# CM4_IO_Conn.net
KiCad netlist of a schematic drawn in Altium Designer
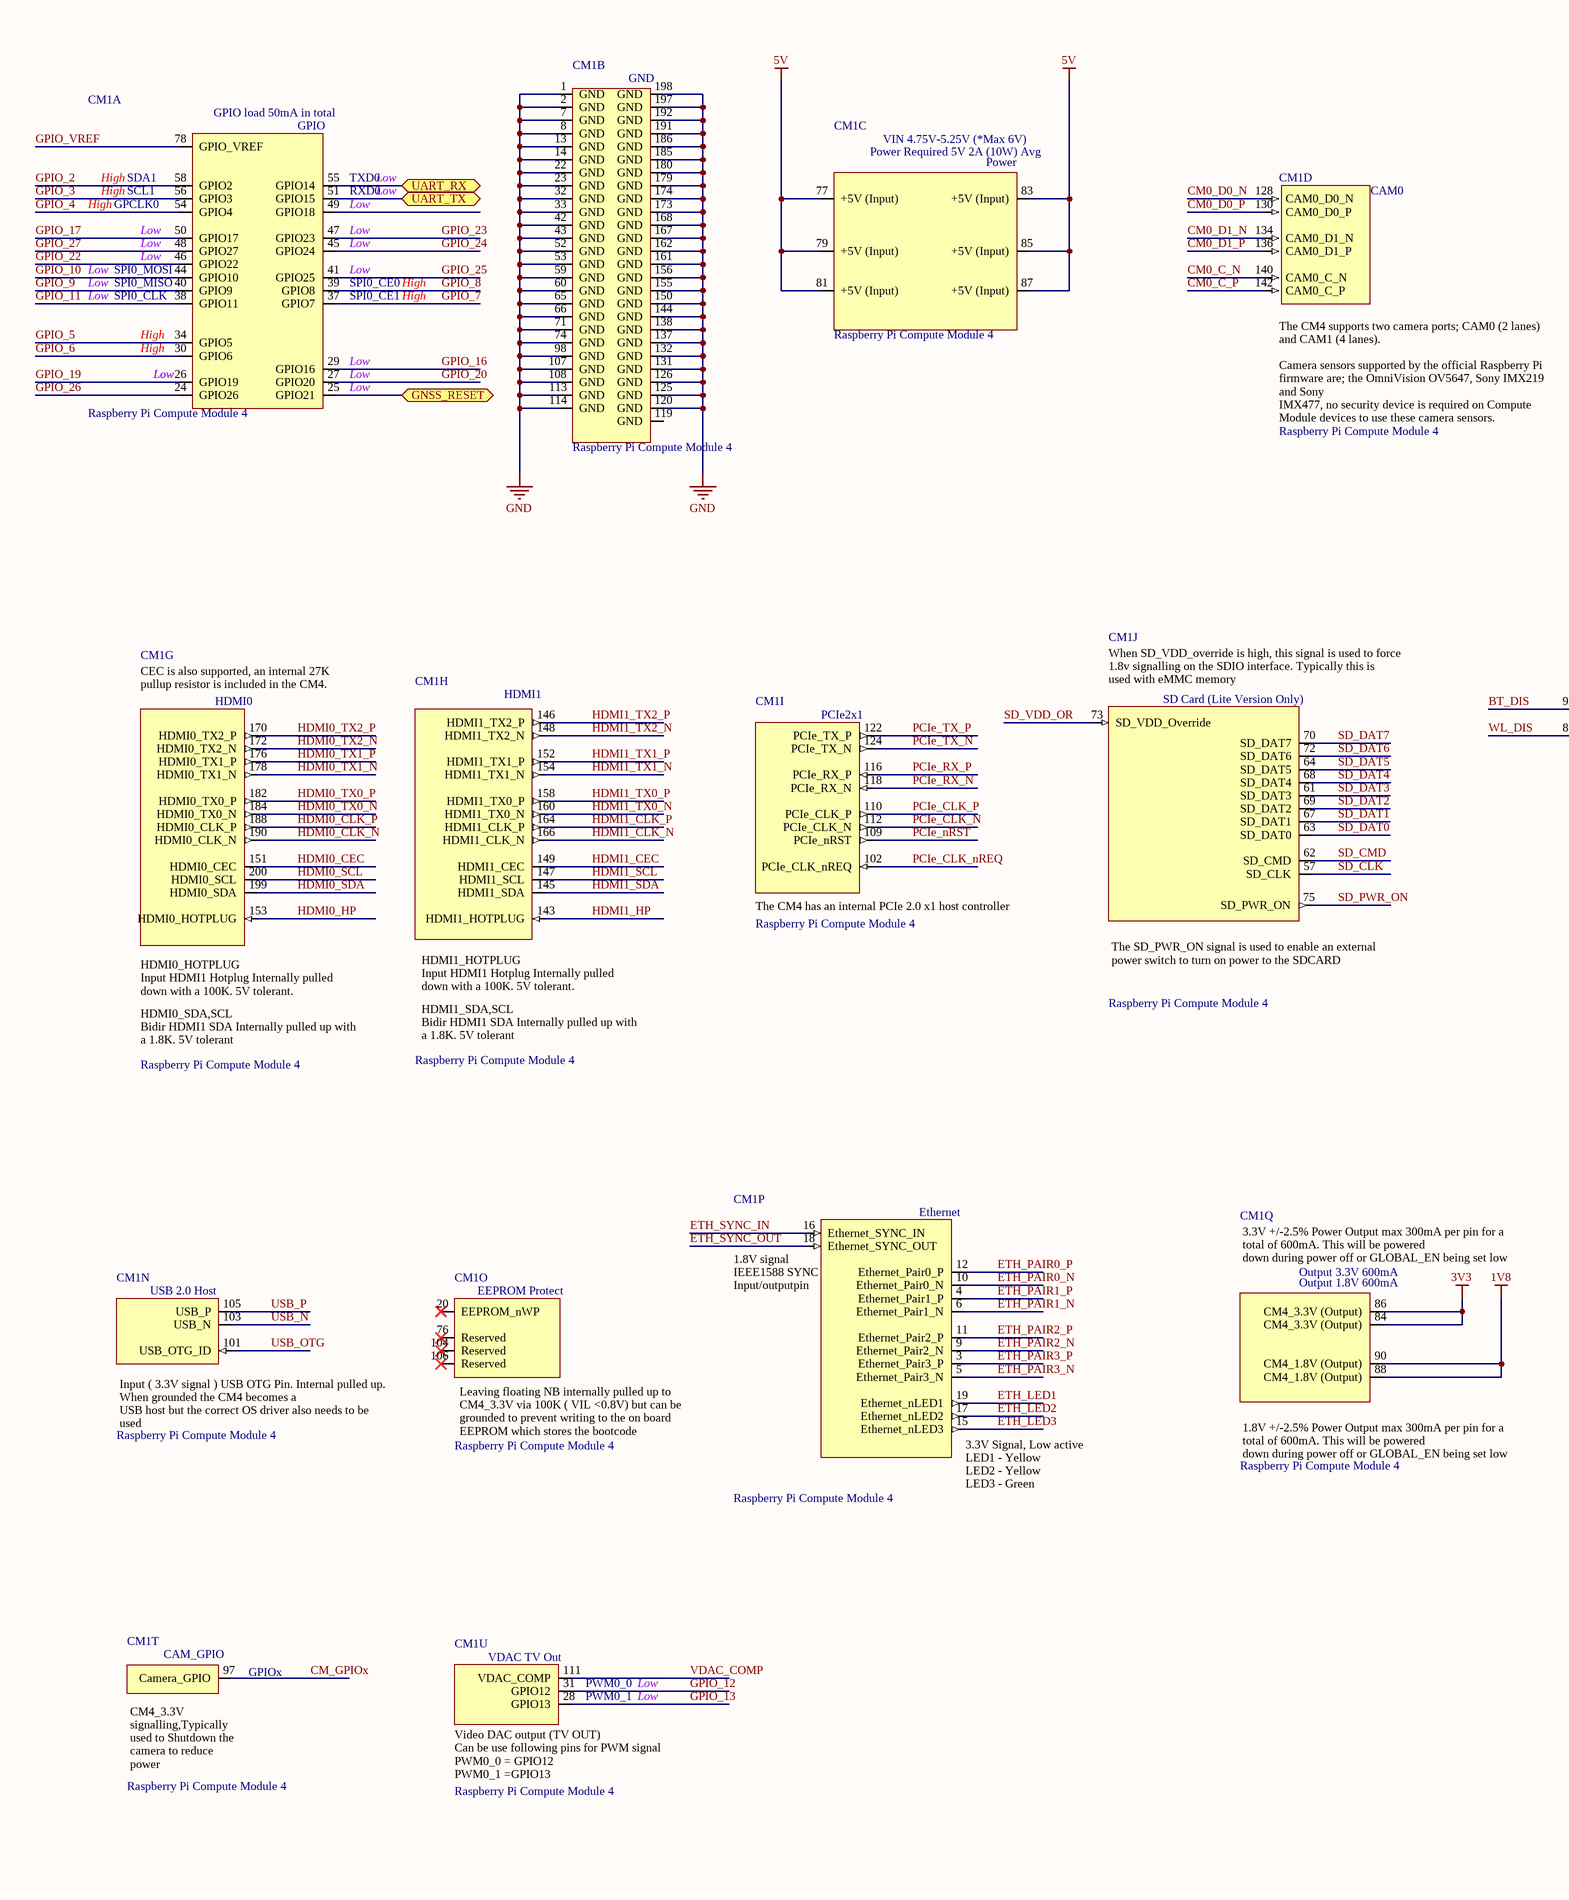
[diagram p0: CM4_IO_Conn.SchDoc, left]
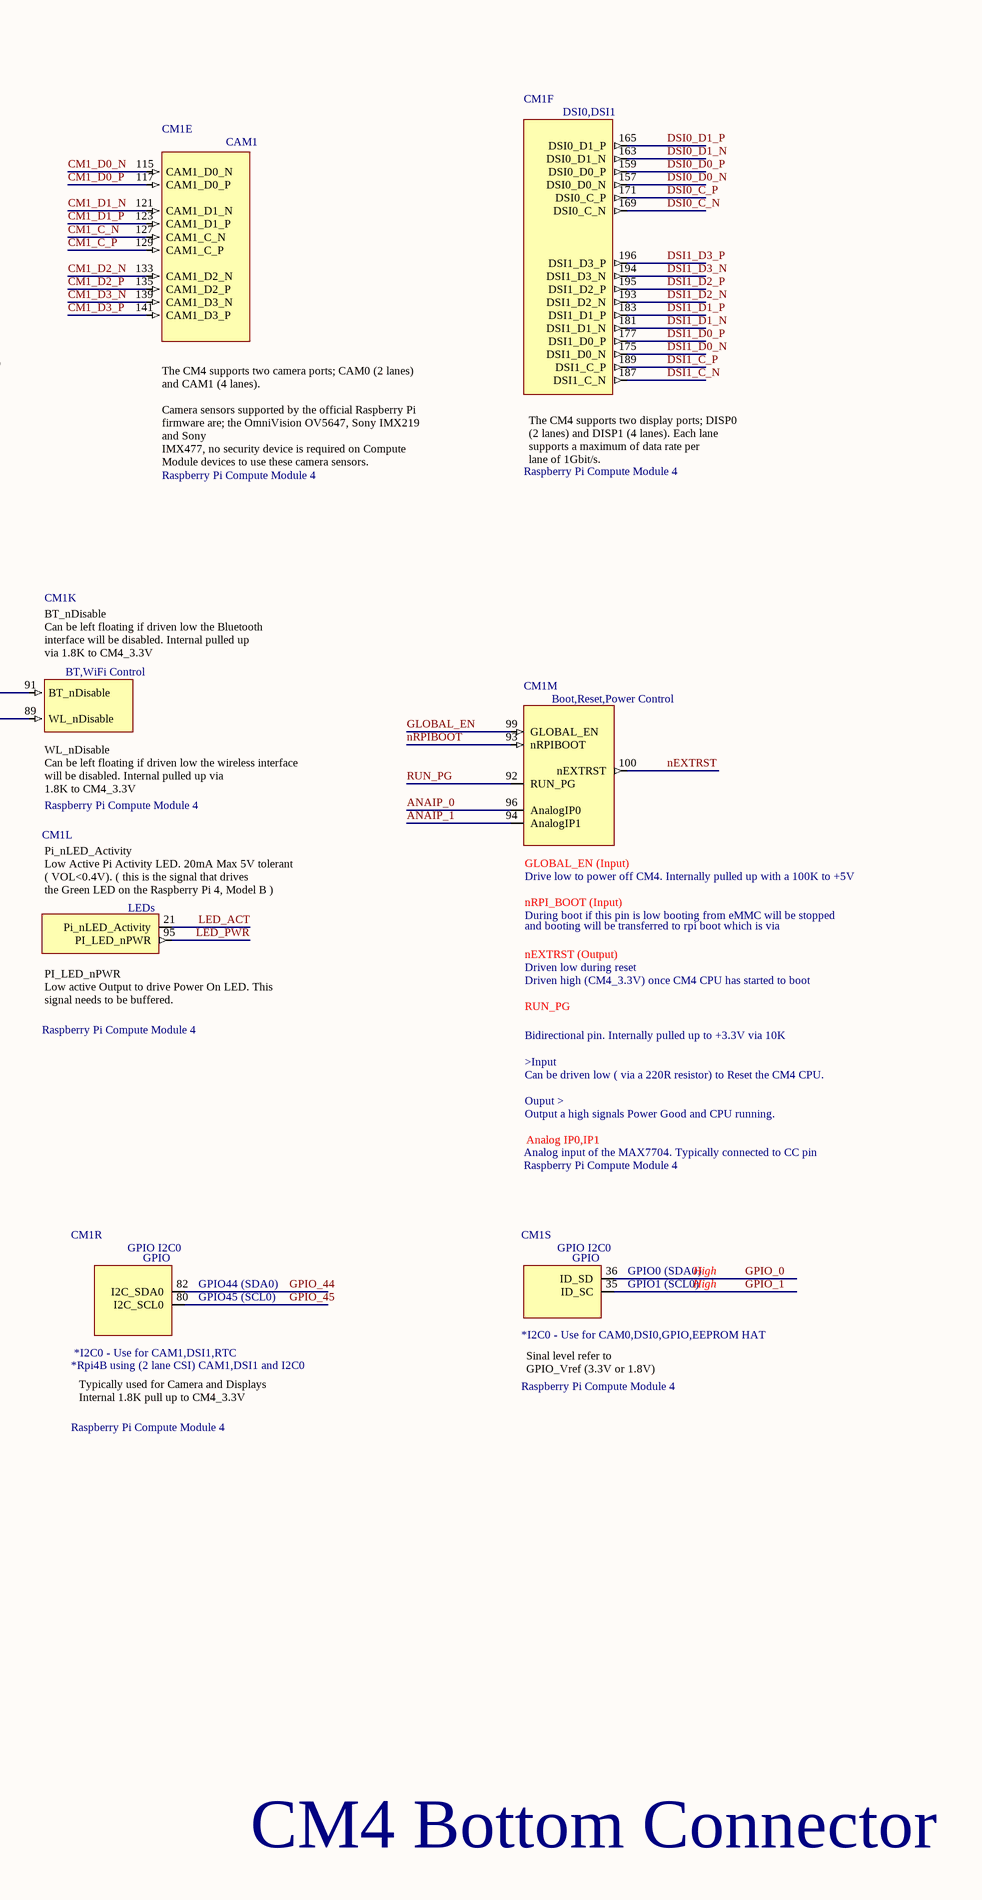
[diagram p1: CM4_IO_Conn.SchDoc, right]

(export (version "E")
  (design (tool "Eeschema 10.0.6"))
  (components
    (comp (ref "CM1")
      (value "Raspberry Pi Compute Module 4")
      (footprint "CM4-F40C-100DS-0.4v_1.5mm_0mm")
      (description "Raspberry Pi Compute Module 4 by Amornthep Phunsin")
      (libsource (lib "CM4") (part "CM4"))
    )
  )
  (nets
    (net (code "1") (name "/ANAIP_0") (class "Default")
      (node (ref "CM1") (pin "96") (pinfunction "AnalogIP0_96") (pintype "passive"))
    )
    (net (code "2") (name "/ANAIP_1") (class "Default")
      (node (ref "CM1") (pin "94") (pinfunction "AnalogIP1_94") (pintype "passive"))
    )
    (net (code "3") (name "/BT_DIS") (class "Default")
      (node (ref "CM1") (pin "91") (pinfunction "BT_nDisable_91") (pintype "input"))
    )
    (net (code "4") (name "/CM0_C_N") (class "Default")
      (node (ref "CM1") (pin "140") (pinfunction "CAM0_C_N_140") (pintype "input"))
    )
    (net (code "5") (name "/CM0_C_P") (class "Default")
      (node (ref "CM1") (pin "142") (pinfunction "CAM0_C_P_142") (pintype "input"))
    )
    (net (code "6") (name "/CM0_D0_N") (class "Default")
      (node (ref "CM1") (pin "128") (pinfunction "CAM0_D0_N_128") (pintype "input"))
    )
    (net (code "7") (name "/CM0_D0_P") (class "Default")
      (node (ref "CM1") (pin "130") (pinfunction "CAM0_D0_P_130") (pintype "input"))
    )
    (net (code "8") (name "/CM0_D1_N") (class "Default")
      (node (ref "CM1") (pin "134") (pinfunction "CAM0_D1_N_134") (pintype "input"))
    )
    (net (code "9") (name "/CM0_D1_P") (class "Default")
      (node (ref "CM1") (pin "136") (pinfunction "CAM0_D1_P_136") (pintype "input"))
    )
    (net (code "10") (name "/CM1_C_N") (class "Default")
      (node (ref "CM1") (pin "127") (pinfunction "CAM1_C_N_127") (pintype "input"))
    )
    (net (code "11") (name "/CM1_C_P") (class "Default")
      (node (ref "CM1") (pin "129") (pinfunction "CAM1_C_P_129") (pintype "input"))
    )
    (net (code "12") (name "/CM1_D0_N") (class "Default")
      (node (ref "CM1") (pin "115") (pinfunction "CAM1_D0_N_115") (pintype "input"))
    )
    (net (code "13") (name "/CM1_D0_P") (class "Default")
      (node (ref "CM1") (pin "117") (pinfunction "CAM1_D0_P_117") (pintype "input"))
    )
    (net (code "14") (name "/CM1_D1_N") (class "Default")
      (node (ref "CM1") (pin "121") (pinfunction "CAM1_D1_N_121") (pintype "input"))
    )
    (net (code "15") (name "/CM1_D1_P") (class "Default")
      (node (ref "CM1") (pin "123") (pinfunction "CAM1_D1_P_123") (pintype "input"))
    )
    (net (code "16") (name "/CM1_D2_N") (class "Default")
      (node (ref "CM1") (pin "133") (pinfunction "CAM1_D2_N_133") (pintype "input"))
    )
    (net (code "17") (name "/CM1_D2_P") (class "Default")
      (node (ref "CM1") (pin "135") (pinfunction "CAM1_D2_P_135") (pintype "input"))
    )
    (net (code "18") (name "/CM1_D3_N") (class "Default")
      (node (ref "CM1") (pin "139") (pinfunction "CAM1_D3_N_139") (pintype "input"))
    )
    (net (code "19") (name "/CM1_D3_P") (class "Default")
      (node (ref "CM1") (pin "141") (pinfunction "CAM1_D3_P_141") (pintype "input"))
    )
    (net (code "20") (name "/CM_GPIOx") (class "Default")
      (node (ref "CM1") (pin "97") (pinfunction "Camera_GPIO_97") (pintype "passive"))
    )
    (net (code "21") (name "/DSI0_C_N") (class "Default")
      (node (ref "CM1") (pin "169") (pinfunction "DSI0_C_N_169") (pintype "output"))
    )
    (net (code "22") (name "/DSI0_C_P") (class "Default")
      (node (ref "CM1") (pin "171") (pinfunction "DSI0_C_P_171") (pintype "output"))
    )
    (net (code "23") (name "/DSI0_D0_N") (class "Default")
      (node (ref "CM1") (pin "157") (pinfunction "DSI0_D0_N_157") (pintype "output"))
    )
    (net (code "24") (name "/DSI0_D0_P") (class "Default")
      (node (ref "CM1") (pin "159") (pinfunction "DSI0_D0_P_159") (pintype "output"))
    )
    (net (code "25") (name "/DSI0_D1_N") (class "Default")
      (node (ref "CM1") (pin "163") (pinfunction "DSI0_D1_N_163") (pintype "output"))
    )
    (net (code "26") (name "/DSI0_D1_P") (class "Default")
      (node (ref "CM1") (pin "165") (pinfunction "DSI0_D1_P_165") (pintype "output"))
    )
    (net (code "27") (name "/DSI1_C_N") (class "Default")
      (node (ref "CM1") (pin "187") (pinfunction "DSI1_C_N_187") (pintype "output"))
    )
    (net (code "28") (name "/DSI1_C_P") (class "Default")
      (node (ref "CM1") (pin "189") (pinfunction "DSI1_C_P_189") (pintype "output"))
    )
    (net (code "29") (name "/DSI1_D0_N") (class "Default")
      (node (ref "CM1") (pin "175") (pinfunction "DSI1_D0_N_175") (pintype "output"))
    )
    (net (code "30") (name "/DSI1_D0_P") (class "Default")
      (node (ref "CM1") (pin "177") (pinfunction "DSI1_D0_P_177") (pintype "output"))
    )
    (net (code "31") (name "/DSI1_D1_N") (class "Default")
      (node (ref "CM1") (pin "181") (pinfunction "DSI1_D1_N_181") (pintype "output"))
    )
    (net (code "32") (name "/DSI1_D1_P") (class "Default")
      (node (ref "CM1") (pin "183") (pinfunction "DSI1_D1_P_183") (pintype "output"))
    )
    (net (code "33") (name "/DSI1_D2_N") (class "Default")
      (node (ref "CM1") (pin "193") (pinfunction "DSI1_D2_N_193") (pintype "output"))
    )
    (net (code "34") (name "/DSI1_D2_P") (class "Default")
      (node (ref "CM1") (pin "195") (pinfunction "DSI1_D2_P_195") (pintype "output"))
    )
    (net (code "35") (name "/DSI1_D3_N") (class "Default")
      (node (ref "CM1") (pin "194") (pinfunction "DSI1_D3_N_194") (pintype "output"))
    )
    (net (code "36") (name "/DSI1_D3_P") (class "Default")
      (node (ref "CM1") (pin "196") (pinfunction "DSI1_D3_P_196") (pintype "output"))
    )
    (net (code "37") (name "/ETH_LED1") (class "Default")
      (node (ref "CM1") (pin "19") (pinfunction "Ethernet_nLED1_19") (pintype "output"))
    )
    (net (code "38") (name "/ETH_LED2") (class "Default")
      (node (ref "CM1") (pin "17") (pinfunction "Ethernet_nLED2_17") (pintype "output"))
    )
    (net (code "39") (name "/ETH_LED3") (class "Default")
      (node (ref "CM1") (pin "15") (pinfunction "Ethernet_nLED3_15") (pintype "output"))
    )
    (net (code "40") (name "/ETH_PAIR0_N") (class "Default")
      (node (ref "CM1") (pin "10") (pinfunction "Ethernet_Pair0_N_10") (pintype "passive"))
    )
    (net (code "41") (name "/ETH_PAIR0_P") (class "Default")
      (node (ref "CM1") (pin "12") (pinfunction "Ethernet_Pair0_P_12") (pintype "passive"))
    )
    (net (code "42") (name "/ETH_PAIR1_N") (class "Default")
      (node (ref "CM1") (pin "6") (pinfunction "Ethernet_Pair1_N_6") (pintype "passive"))
    )
    (net (code "43") (name "/ETH_PAIR1_P") (class "Default")
      (node (ref "CM1") (pin "4") (pinfunction "Ethernet_Pair1_P_4") (pintype "passive"))
    )
    (net (code "44") (name "/ETH_PAIR2_N") (class "Default")
      (node (ref "CM1") (pin "9") (pinfunction "Ethernet_Pair2_N_9") (pintype "passive"))
    )
    (net (code "45") (name "/ETH_PAIR2_P") (class "Default")
      (node (ref "CM1") (pin "11") (pinfunction "Ethernet_Pair2_P_11") (pintype "passive"))
    )
    (net (code "46") (name "/ETH_PAIR3_N") (class "Default")
      (node (ref "CM1") (pin "5") (pinfunction "Ethernet_Pair3_N_5") (pintype "passive"))
    )
    (net (code "47") (name "/ETH_PAIR3_P") (class "Default")
      (node (ref "CM1") (pin "3") (pinfunction "Ethernet_Pair3_P_3") (pintype "passive"))
    )
    (net (code "48") (name "/ETH_SYNC_IN") (class "Default")
      (node (ref "CM1") (pin "16") (pinfunction "Ethernet_SYNC_IN_16") (pintype "input"))
    )
    (net (code "49") (name "/ETH_SYNC_OUT") (class "Default")
      (node (ref "CM1") (pin "18") (pinfunction "Ethernet_SYNC_OUT_18") (pintype "input"))
    )
    (net (code "50") (name "/GLOBAL_EN") (class "Default")
      (node (ref "CM1") (pin "99") (pinfunction "GLOBAL_EN_99") (pintype "input"))
    )
    (net (code "51") (name "/GNSS_RESET") (class "Default")
      (node (ref "CM1") (pin "25") (pinfunction "GPIO21_25") (pintype "passive"))
    )
    (net (code "52") (name "/GPIO_0") (class "Default")
      (node (ref "CM1") (pin "36") (pinfunction "ID_SD_36") (pintype "passive"))
    )
    (net (code "53") (name "/GPIO_1") (class "Default")
      (node (ref "CM1") (pin "35") (pinfunction "ID_SC_35") (pintype "passive"))
    )
    (net (code "54") (name "/GPIO_2") (class "Default")
      (node (ref "CM1") (pin "58") (pinfunction "GPIO2_58") (pintype "passive"))
    )
    (net (code "55") (name "/GPIO_3") (class "Default")
      (node (ref "CM1") (pin "56") (pinfunction "GPIO3_56") (pintype "passive"))
    )
    (net (code "56") (name "/GPIO_4") (class "Default")
      (node (ref "CM1") (pin "54") (pinfunction "GPIO4_54") (pintype "passive"))
    )
    (net (code "57") (name "/GPIO_5") (class "Default")
      (node (ref "CM1") (pin "34") (pinfunction "GPIO5_34") (pintype "passive"))
    )
    (net (code "58") (name "/GPIO_6") (class "Default")
      (node (ref "CM1") (pin "30") (pinfunction "GPIO6_30") (pintype "passive"))
    )
    (net (code "59") (name "/GPIO_7") (class "Default")
      (node (ref "CM1") (pin "37") (pinfunction "GPIO7_37") (pintype "passive"))
    )
    (net (code "60") (name "/GPIO_8") (class "Default")
      (node (ref "CM1") (pin "39") (pinfunction "GPIO8_39") (pintype "passive"))
    )
    (net (code "61") (name "/GPIO_9") (class "Default")
      (node (ref "CM1") (pin "40") (pinfunction "GPIO9_40") (pintype "passive"))
    )
    (net (code "62") (name "/GPIO_10") (class "Default")
      (node (ref "CM1") (pin "44") (pinfunction "GPIO10_44") (pintype "passive"))
    )
    (net (code "63") (name "/GPIO_11") (class "Default")
      (node (ref "CM1") (pin "38") (pinfunction "GPIO11_38") (pintype "passive"))
    )
    (net (code "64") (name "/GPIO_12") (class "Default")
      (node (ref "CM1") (pin "31") (pinfunction "GPIO12_31") (pintype "passive"))
    )
    (net (code "65") (name "/GPIO_13") (class "Default")
      (node (ref "CM1") (pin "28") (pinfunction "GPIO13_28") (pintype "passive"))
    )
    (net (code "66") (name "/GPIO_16") (class "Default")
      (node (ref "CM1") (pin "29") (pinfunction "GPIO16_29") (pintype "passive"))
    )
    (net (code "67") (name "/GPIO_17") (class "Default")
      (node (ref "CM1") (pin "50") (pinfunction "GPIO17_50") (pintype "passive"))
    )
    (net (code "68") (name "/GPIO_19") (class "Default")
      (node (ref "CM1") (pin "26") (pinfunction "GPIO19_26") (pintype "passive"))
    )
    (net (code "69") (name "/GPIO_20") (class "Default")
      (node (ref "CM1") (pin "27") (pinfunction "GPIO20_27") (pintype "passive"))
    )
    (net (code "70") (name "/GPIO_22") (class "Default")
      (node (ref "CM1") (pin "46") (pinfunction "GPIO22_46") (pintype "passive"))
    )
    (net (code "71") (name "/GPIO_23") (class "Default")
      (node (ref "CM1") (pin "47") (pinfunction "GPIO23_47") (pintype "passive"))
    )
    (net (code "72") (name "/GPIO_24") (class "Default")
      (node (ref "CM1") (pin "45") (pinfunction "GPIO24_45") (pintype "passive"))
    )
    (net (code "73") (name "/GPIO_25") (class "Default")
      (node (ref "CM1") (pin "41") (pinfunction "GPIO25_41") (pintype "passive"))
    )
    (net (code "74") (name "/GPIO_26") (class "Default")
      (node (ref "CM1") (pin "24") (pinfunction "GPIO26_24") (pintype "passive"))
    )
    (net (code "75") (name "/GPIO_27") (class "Default")
      (node (ref "CM1") (pin "48") (pinfunction "GPIO27_48") (pintype "passive"))
    )
    (net (code "76") (name "/GPIO_44") (class "Default")
      (node (ref "CM1") (pin "82") (pinfunction "I2C_SDA0_82") (pintype "passive"))
    )
    (net (code "77") (name "/GPIO_45") (class "Default")
      (node (ref "CM1") (pin "80") (pinfunction "I2C_SCL0_80") (pintype "passive"))
    )
    (net (code "78") (name "/GPIO_VREF") (class "Default")
      (node (ref "CM1") (pin "78") (pinfunction "GPIO_VREF_78") (pintype "power_in"))
    )
    (net (code "79") (name "/HDMI0_CEC") (class "Default")
      (node (ref "CM1") (pin "151") (pinfunction "HDMI0_CEC_151") (pintype "open_collector"))
    )
    (net (code "80") (name "/HDMI0_CLK_N") (class "Default")
      (node (ref "CM1") (pin "190") (pinfunction "HDMI0_CLK_N_190") (pintype "output"))
    )
    (net (code "81") (name "/HDMI0_CLK_P") (class "Default")
      (node (ref "CM1") (pin "188") (pinfunction "HDMI0_CLK_P_188") (pintype "output"))
    )
    (net (code "82") (name "/HDMI0_HP") (class "Default")
      (node (ref "CM1") (pin "153") (pinfunction "HDMI0_HOTPLUG_153") (pintype "input"))
    )
    (net (code "83") (name "/HDMI0_SCL") (class "Default")
      (node (ref "CM1") (pin "200") (pinfunction "HDMI0_SCL_200") (pintype "open_collector"))
    )
    (net (code "84") (name "/HDMI0_SDA") (class "Default")
      (node (ref "CM1") (pin "199") (pinfunction "HDMI0_SDA_199") (pintype "bidirectional"))
    )
    (net (code "85") (name "/HDMI0_TX0_N") (class "Default")
      (node (ref "CM1") (pin "184") (pinfunction "HDMI0_TX0_N_184") (pintype "output"))
    )
    (net (code "86") (name "/HDMI0_TX0_P") (class "Default")
      (node (ref "CM1") (pin "182") (pinfunction "HDMI0_TX0_P_182") (pintype "output"))
    )
    (net (code "87") (name "/HDMI0_TX1_N") (class "Default")
      (node (ref "CM1") (pin "178") (pinfunction "HDMI0_TX1_N_178") (pintype "output"))
    )
    (net (code "88") (name "/HDMI0_TX1_P") (class "Default")
      (node (ref "CM1") (pin "176") (pinfunction "HDMI0_TX1_P_176") (pintype "output"))
    )
    (net (code "89") (name "/HDMI0_TX2_N") (class "Default")
      (node (ref "CM1") (pin "172") (pinfunction "HDMI0_TX2_N_172") (pintype "output"))
    )
    (net (code "90") (name "/HDMI0_TX2_P") (class "Default")
      (node (ref "CM1") (pin "170") (pinfunction "HDMI0_TX2_P_170") (pintype "output"))
    )
    (net (code "91") (name "/HDMI1_CEC") (class "Default")
      (node (ref "CM1") (pin "149") (pinfunction "HDMI1_CEC_149") (pintype "open_collector"))
    )
    (net (code "92") (name "/HDMI1_CLK_N") (class "Default")
      (node (ref "CM1") (pin "166") (pinfunction "HDMI1_CLK_N_166") (pintype "output"))
    )
    (net (code "93") (name "/HDMI1_CLK_P") (class "Default")
      (node (ref "CM1") (pin "164") (pinfunction "HDMI1_CLK_P_164") (pintype "output"))
    )
    (net (code "94") (name "/HDMI1_HP") (class "Default")
      (node (ref "CM1") (pin "143") (pinfunction "HDMI1_HOTPLUG_143") (pintype "input"))
    )
    (net (code "95") (name "/HDMI1_SCL") (class "Default")
      (node (ref "CM1") (pin "147") (pinfunction "HDMI1_SCL_147") (pintype "open_collector"))
    )
    (net (code "96") (name "/HDMI1_SDA") (class "Default")
      (node (ref "CM1") (pin "145") (pinfunction "HDMI1_SDA_145") (pintype "bidirectional"))
    )
    (net (code "97") (name "/HDMI1_TX0_N") (class "Default")
      (node (ref "CM1") (pin "160") (pinfunction "HDMI1_TX0_N_160") (pintype "output"))
    )
    (net (code "98") (name "/HDMI1_TX0_P") (class "Default")
      (node (ref "CM1") (pin "158") (pinfunction "HDMI1_TX0_P_158") (pintype "output"))
    )
    (net (code "99") (name "/HDMI1_TX1_N") (class "Default")
      (node (ref "CM1") (pin "154") (pinfunction "HDMI1_TX1_N_154") (pintype "output"))
    )
    (net (code "100") (name "/HDMI1_TX1_P") (class "Default")
      (node (ref "CM1") (pin "152") (pinfunction "HDMI1_TX1_P_152") (pintype "output"))
    )
    (net (code "101") (name "/HDMI1_TX2_N") (class "Default")
      (node (ref "CM1") (pin "148") (pinfunction "HDMI1_TX2_N_148") (pintype "output"))
    )
    (net (code "102") (name "/HDMI1_TX2_P") (class "Default")
      (node (ref "CM1") (pin "146") (pinfunction "HDMI1_TX2_P_146") (pintype "output"))
    )
    (net (code "103") (name "/LED_ACT") (class "Default")
      (node (ref "CM1") (pin "21") (pinfunction "Pi_nLED_Activity_21") (pintype "open_collector"))
    )
    (net (code "104") (name "/LED_PWR") (class "Default")
      (node (ref "CM1") (pin "95") (pinfunction "PI_LED_nPWR_95") (pintype "output"))
    )
    (net (code "105") (name "/PCIe_CLK_N") (class "Default")
      (node (ref "CM1") (pin "112") (pinfunction "PCIe_CLK_N_112") (pintype "output"))
    )
    (net (code "106") (name "/PCIe_CLK_P") (class "Default")
      (node (ref "CM1") (pin "110") (pinfunction "PCIe_CLK_P_110") (pintype "output"))
    )
    (net (code "107") (name "/PCIe_CLK_nREQ") (class "Default")
      (node (ref "CM1") (pin "102") (pinfunction "PCIe_CLK_nREQ_102") (pintype "input"))
    )
    (net (code "108") (name "/PCIe_RX_N") (class "Default")
      (node (ref "CM1") (pin "118") (pinfunction "PCIe_RX_N_118") (pintype "input"))
    )
    (net (code "109") (name "/PCIe_RX_P") (class "Default")
      (node (ref "CM1") (pin "116") (pinfunction "PCIe_RX_P_116") (pintype "input"))
    )
    (net (code "110") (name "/PCIe_TX_N") (class "Default")
      (node (ref "CM1") (pin "124") (pinfunction "PCIe_TX_N_124") (pintype "output"))
    )
    (net (code "111") (name "/PCIe_TX_P") (class "Default")
      (node (ref "CM1") (pin "122") (pinfunction "PCIe_TX_P_122") (pintype "output"))
    )
    (net (code "112") (name "/PCIe_nRST") (class "Default")
      (node (ref "CM1") (pin "109") (pinfunction "PCIe_nRST_109") (pintype "output"))
    )
    (net (code "113") (name "/RUN_PG") (class "Default")
      (node (ref "CM1") (pin "92") (pinfunction "RUN_PG_92") (pintype "passive"))
    )
    (net (code "114") (name "/SD_CLK") (class "Default")
      (node (ref "CM1") (pin "57") (pinfunction "SD_CLK_57") (pintype "passive"))
    )
    (net (code "115") (name "/SD_CMD") (class "Default")
      (node (ref "CM1") (pin "62") (pinfunction "SD_CMD_62") (pintype "passive"))
    )
    (net (code "116") (name "/SD_DAT0") (class "Default")
      (node (ref "CM1") (pin "63") (pinfunction "SD_DAT0_63") (pintype "passive"))
    )
    (net (code "117") (name "/SD_DAT1") (class "Default")
      (node (ref "CM1") (pin "67") (pinfunction "SD_DAT1_67") (pintype "passive"))
    )
    (net (code "118") (name "/SD_DAT2") (class "Default")
      (node (ref "CM1") (pin "69") (pinfunction "SD_DAT2_69") (pintype "passive"))
    )
    (net (code "119") (name "/SD_DAT3") (class "Default")
      (node (ref "CM1") (pin "61") (pinfunction "SD_DAT3_61") (pintype "passive"))
    )
    (net (code "120") (name "/SD_DAT4") (class "Default")
      (node (ref "CM1") (pin "68") (pinfunction "SD_DAT4_68") (pintype "passive"))
    )
    (net (code "121") (name "/SD_DAT5") (class "Default")
      (node (ref "CM1") (pin "64") (pinfunction "SD_DAT5_64") (pintype "passive"))
    )
    (net (code "122") (name "/SD_DAT6") (class "Default")
      (node (ref "CM1") (pin "72") (pinfunction "SD_DAT6_72") (pintype "passive"))
    )
    (net (code "123") (name "/SD_DAT7") (class "Default")
      (node (ref "CM1") (pin "70") (pinfunction "SD_DAT7_70") (pintype "passive"))
    )
    (net (code "124") (name "/SD_PWR_ON") (class "Default")
      (node (ref "CM1") (pin "75") (pinfunction "SD_PWR_ON_75") (pintype "output"))
    )
    (net (code "125") (name "/SD_VDD_OR") (class "Default")
      (node (ref "CM1") (pin "73") (pinfunction "SD_VDD_Override_73") (pintype "input"))
    )
    (net (code "126") (name "/UART_RX") (class "Default")
      (node (ref "CM1") (pin "55") (pinfunction "GPIO14_55") (pintype "passive"))
    )
    (net (code "127") (name "/UART_TX") (class "Default")
      (node (ref "CM1") (pin "51") (pinfunction "GPIO15_51") (pintype "passive"))
    )
    (net (code "128") (name "/USB_N") (class "Default")
      (node (ref "CM1") (pin "103") (pinfunction "USB_N_103") (pintype "passive"))
    )
    (net (code "129") (name "/USB_OTG") (class "Default")
      (node (ref "CM1") (pin "101") (pinfunction "USB_OTG_ID_101") (pintype "input"))
    )
    (net (code "130") (name "/USB_P") (class "Default")
      (node (ref "CM1") (pin "105") (pinfunction "USB_P_105") (pintype "passive"))
    )
    (net (code "131") (name "/VDAC_COMP") (class "Default")
      (node (ref "CM1") (pin "111") (pinfunction "VDAC_COMP_111") (pintype "passive"))
    )
    (net (code "132") (name "/WL_DIS") (class "Default")
      (node (ref "CM1") (pin "89") (pinfunction "WL_nDisable_89") (pintype "input"))
    )
    (net (code "133") (name "/nEXTRST") (class "Default")
      (node (ref "CM1") (pin "100") (pinfunction "nEXTRST_100") (pintype "output"))
    )
    (net (code "134") (name "/nRPIBOOT") (class "Default")
      (node (ref "CM1") (pin "93") (pinfunction "nRPIBOOT_93") (pintype "input"))
    )
    (net (code "135") (name "1V8") (class "Default")
      (node (ref "CM1") (pin "88") (pinfunction "CM4_1.8V_(Output)_88") (pintype "power_in"))
      (node (ref "CM1") (pin "90") (pinfunction "CM4_1.8V_(Output)_90") (pintype "power_in"))
    )
    (net (code "136") (name "3V3") (class "Default")
      (node (ref "CM1") (pin "84") (pinfunction "CM4_3.3V_(Output)_84") (pintype "power_in"))
      (node (ref "CM1") (pin "86") (pinfunction "CM4_3.3V_(Output)_86") (pintype "power_in"))
    )
    (net (code "137") (name "5V") (class "Default")
      (node (ref "CM1") (pin "77") (pinfunction "+5V_(Input)_77") (pintype "power_in"))
      (node (ref "CM1") (pin "79") (pinfunction "+5V_(Input)_79") (pintype "power_in"))
      (node (ref "CM1") (pin "81") (pinfunction "+5V_(Input)_81") (pintype "power_in"))
      (node (ref "CM1") (pin "83") (pinfunction "+5V_(Input)_83") (pintype "power_in"))
      (node (ref "CM1") (pin "85") (pinfunction "+5V_(Input)_85") (pintype "power_in"))
      (node (ref "CM1") (pin "87") (pinfunction "+5V_(Input)_87") (pintype "power_in"))
    )
    (net (code "138") (name "GND") (class "Default")
      (node (ref "CM1") (pin "1") (pinfunction "GND_1") (pintype "power_in"))
      (node (ref "CM1") (pin "107") (pinfunction "GND_107") (pintype "power_in"))
      (node (ref "CM1") (pin "108") (pinfunction "GND_108") (pintype "power_in"))
      (node (ref "CM1") (pin "113") (pinfunction "GND_113") (pintype "power_in"))
      (node (ref "CM1") (pin "114") (pinfunction "GND_114") (pintype "power_in"))
      (node (ref "CM1") (pin "120") (pinfunction "GND_120") (pintype "power_in"))
      (node (ref "CM1") (pin "125") (pinfunction "GND_125") (pintype "power_in"))
      (node (ref "CM1") (pin "126") (pinfunction "GND_126") (pintype "power_in"))
      (node (ref "CM1") (pin "13") (pinfunction "GND_13") (pintype "power_in"))
      (node (ref "CM1") (pin "131") (pinfunction "GND_131") (pintype "power_in"))
      (node (ref "CM1") (pin "132") (pinfunction "GND_132") (pintype "power_in"))
      (node (ref "CM1") (pin "137") (pinfunction "GND_137") (pintype "power_in"))
      (node (ref "CM1") (pin "138") (pinfunction "GND_138") (pintype "power_in"))
      (node (ref "CM1") (pin "14") (pinfunction "GND_14") (pintype "power_in"))
      (node (ref "CM1") (pin "144") (pinfunction "GND_144") (pintype "power_in"))
      (node (ref "CM1") (pin "150") (pinfunction "GND_150") (pintype "power_in"))
      (node (ref "CM1") (pin "155") (pinfunction "GND_155") (pintype "power_in"))
      (node (ref "CM1") (pin "156") (pinfunction "GND_156") (pintype "power_in"))
      (node (ref "CM1") (pin "161") (pinfunction "GND_161") (pintype "power_in"))
      (node (ref "CM1") (pin "162") (pinfunction "GND_162") (pintype "power_in"))
      (node (ref "CM1") (pin "167") (pinfunction "GND_167") (pintype "power_in"))
      (node (ref "CM1") (pin "168") (pinfunction "GND_168") (pintype "power_in"))
      (node (ref "CM1") (pin "173") (pinfunction "GND_173") (pintype "power_in"))
      (node (ref "CM1") (pin "174") (pinfunction "GND_174") (pintype "power_in"))
      (node (ref "CM1") (pin "179") (pinfunction "GND_179") (pintype "power_in"))
      (node (ref "CM1") (pin "180") (pinfunction "GND_180") (pintype "power_in"))
      (node (ref "CM1") (pin "185") (pinfunction "GND_185") (pintype "power_in"))
      (node (ref "CM1") (pin "186") (pinfunction "GND_186") (pintype "power_in"))
      (node (ref "CM1") (pin "191") (pinfunction "GND_191") (pintype "power_in"))
      (node (ref "CM1") (pin "192") (pinfunction "GND_192") (pintype "power_in"))
      (node (ref "CM1") (pin "197") (pinfunction "GND_197") (pintype "power_in"))
      (node (ref "CM1") (pin "198") (pinfunction "GND_198") (pintype "power_in"))
      (node (ref "CM1") (pin "2") (pinfunction "GND_2") (pintype "power_in"))
      (node (ref "CM1") (pin "22") (pinfunction "GND_22") (pintype "power_in"))
      (node (ref "CM1") (pin "23") (pinfunction "GND_23") (pintype "power_in"))
      (node (ref "CM1") (pin "32") (pinfunction "GND_32") (pintype "power_in"))
      (node (ref "CM1") (pin "33") (pinfunction "GND_33") (pintype "power_in"))
      (node (ref "CM1") (pin "42") (pinfunction "GND_42") (pintype "power_in"))
      (node (ref "CM1") (pin "43") (pinfunction "GND_43") (pintype "power_in"))
      (node (ref "CM1") (pin "52") (pinfunction "GND_52") (pintype "power_in"))
      (node (ref "CM1") (pin "53") (pinfunction "GND_53") (pintype "power_in"))
      (node (ref "CM1") (pin "59") (pinfunction "GND_59") (pintype "power_in"))
      (node (ref "CM1") (pin "60") (pinfunction "GND_60") (pintype "power_in"))
      (node (ref "CM1") (pin "65") (pinfunction "GND_65") (pintype "power_in"))
      (node (ref "CM1") (pin "66") (pinfunction "GND_66") (pintype "power_in"))
      (node (ref "CM1") (pin "7") (pinfunction "GND_7") (pintype "power_in"))
      (node (ref "CM1") (pin "71") (pinfunction "GND_71") (pintype "power_in"))
      (node (ref "CM1") (pin "74") (pinfunction "GND_74") (pintype "power_in"))
      (node (ref "CM1") (pin "8") (pinfunction "GND_8") (pintype "power_in"))
      (node (ref "CM1") (pin "98") (pinfunction "GND_98") (pintype "power_in"))
    )
    (net (code "139") (name "unconnected-(CM1A-GPIO18-Pad49)") (class "Default")
      (node (ref "CM1") (pin "49") (pinfunction "GPIO18_49") (pintype "passive"))
    )
    (net (code "140") (name "unconnected-(CM1B-GND-Pad119)") (class "Default")
      (node (ref "CM1") (pin "119") (pinfunction "GND_119") (pintype "power_in"))
    )
    (net (code "141") (name "unconnected-(CM1O-EEPROM_nWP-Pad20)") (class "Default")
      (node (ref "CM1") (pin "20") (pinfunction "EEPROM_nWP_20") (pintype "passive+no_connect"))
    )
    (net (code "142") (name "unconnected-(CM1O-Reserved-Pad76)") (class "Default")
      (node (ref "CM1") (pin "76") (pinfunction "Reserved_76") (pintype "passive+no_connect"))
    )
    (net (code "143") (name "unconnected-(CM1O-Reserved-Pad104)") (class "Default")
      (node (ref "CM1") (pin "104") (pinfunction "Reserved_104") (pintype "passive+no_connect"))
    )
    (net (code "144") (name "unconnected-(CM1O-Reserved-Pad106)") (class "Default")
      (node (ref "CM1") (pin "106") (pinfunction "Reserved_106") (pintype "passive+no_connect"))
    )
  )
)
